# TSC_PROIECT_SCHEMATIC.net
KiCad netlist of a schematic drawn in EAGLE
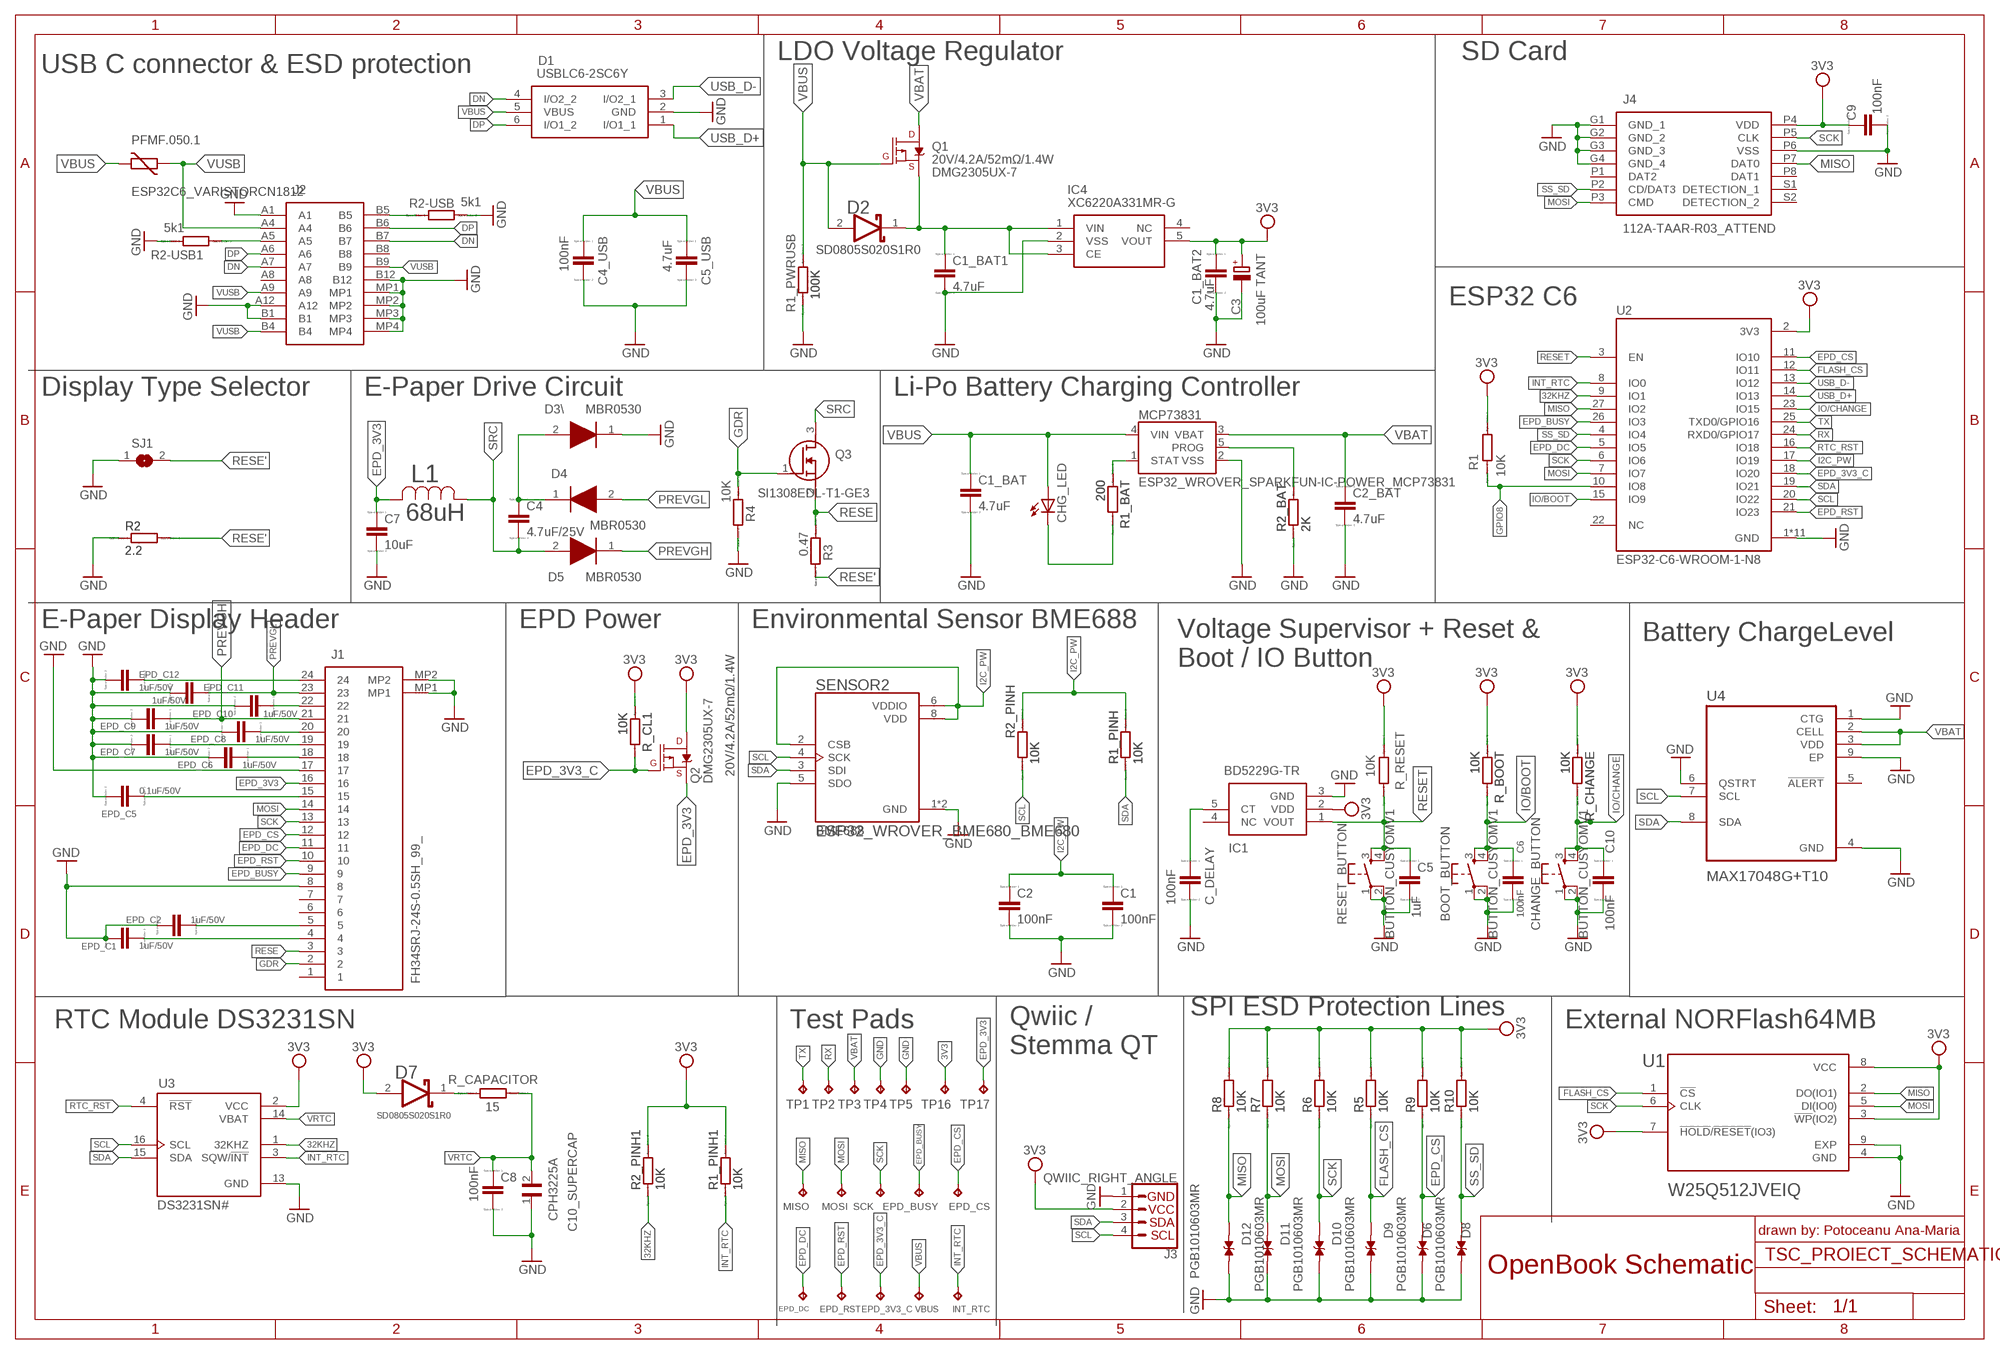
[diagram p0: schematic, sheet 1]

(export (version "E")
  (design (tool "Eeschema 10.0.6"))
  (components
    (comp (ref "BOOT_BUTTON")
      (value "BUTTON_CUSYOMV1")
      (footprint "eagle-import:MYBUTTON")
      (libsource (lib "eagle-import") (part "BUTTON_CUSYOMV1"))
    )
    (comp (ref "C1")
      (value "100nF")
      (footprint "eagle-import:ESP32_WROVER_EAGLE-LTSPICE_C0402")
      (libsource (lib "eagle-import") (part "ESP32_WROVER_EAGLE-LTSPICE_CC0402"))
    )
    (comp (ref "C1_BAT")
      (value "4.7uF")
      (footprint "eagle-import:ESP32_WROVER_EAGLE-LTSPICE_C0402")
      (libsource (lib "eagle-import") (part "EAGLE-LTSPICE_CC0402"))
    )
    (comp (ref "C1_BAT1")
      (value "4.7uF")
      (footprint "eagle-import:ESP32_WROVER_EAGLE-LTSPICE_C0402")
      (libsource (lib "eagle-import") (part "EAGLE-LTSPICE_CC0402"))
    )
    (comp (ref "C1_BAT2")
      (value "4.7uF")
      (footprint "eagle-import:ESP32_WROVER_EAGLE-LTSPICE_C0402")
      (libsource (lib "eagle-import") (part "ESP32_WROVER_EAGLE-LTSPICE_CC0402"))
    )
    (comp (ref "C2")
      (value "100nF")
      (footprint "eagle-import:ESP32_WROVER_EAGLE-LTSPICE_C0402")
      (libsource (lib "eagle-import") (part "ESP32_WROVER_EAGLE-LTSPICE_CC0402"))
    )
    (comp (ref "C2_BAT")
      (value "4.7uF")
      (footprint "eagle-import:ESP32_WROVER_EAGLE-LTSPICE_C0402")
      (libsource (lib "eagle-import") (part "EAGLE-LTSPICE_CC0402"))
    )
    (comp (ref "C3")
      (value "100uF TANT")
      (footprint "eagle-import:RCL_CT3528")
      (libsource (lib "eagle-import") (part "RCL_CPOL-EUCT3528"))
    )
    (comp (ref "C4")
      (value "4.7uF/25V")
      (footprint "eagle-import:ESP32_WROVER_EAGLE-LTSPICE_C0402")
      (libsource (lib "eagle-import") (part "ESP32_WROVER_EAGLE-LTSPICE_CC0402"))
    )
    (comp (ref "C4_USB")
      (value "100nF")
      (footprint "eagle-import:ESP32_WROVER_EAGLE-LTSPICE_C0402")
      (libsource (lib "eagle-import") (part "ESP32_WROVER_EAGLE-LTSPICE_CC0402"))
    )
    (comp (ref "C5")
      (value "1uF")
      (footprint "eagle-import:ESP32_WROVER_EAGLE-LTSPICE_C0402")
      (libsource (lib "eagle-import") (part "EAGLE-LTSPICE_CC0402"))
    )
    (comp (ref "C5_USB")
      (value "4.7uF")
      (footprint "eagle-import:ESP32_WROVER_EAGLE-LTSPICE_C0402")
      (libsource (lib "eagle-import") (part "ESP32_WROVER_EAGLE-LTSPICE_CC0402"))
    )
    (comp (ref "C6")
      (value "100nF")
      (footprint "eagle-import:ESP32_WROVER_EAGLE-LTSPICE_C0402")
      (libsource (lib "eagle-import") (part "EAGLE-LTSPICE_CC0402"))
    )
    (comp (ref "C7")
      (value "10uF")
      (footprint "eagle-import:ESP32_WROVER_EAGLE-LTSPICE_C0402")
      (libsource (lib "eagle-import") (part "ESP32_WROVER_EAGLE-LTSPICE_CC0402"))
    )
    (comp (ref "C8")
      (value "100nF")
      (footprint "eagle-import:ESP32_WROVER_EAGLE-LTSPICE_C0402")
      (libsource (lib "eagle-import") (part "ESP32_WROVER_EAGLE-LTSPICE_CC0402"))
    )
    (comp (ref "C9")
      (value "100nF")
      (footprint "eagle-import:ESP32_WROVER_EAGLE-LTSPICE_C0402")
      (libsource (lib "eagle-import") (part "EAGLE-LTSPICE_CC0402"))
    )
    (comp (ref "C10")
      (value "100nF")
      (footprint "eagle-import:ESP32_WROVER_EAGLE-LTSPICE_C0402")
      (libsource (lib "eagle-import") (part "EAGLE-LTSPICE_CC0402"))
    )
    (comp (ref "C10_SUPERCAP")
      (value "CPH3225A")
      (footprint "eagle-import:CAPCP3225X100N")
      (fields (field (name "MF") "Seiko Instruments"))
      (libsource (lib "eagle-import") (part "CPH3225A"))
    )
    (comp (ref "CHANGE_BUTTON")
      (value "BUTTON_CUSYOMV1")
      (footprint "eagle-import:MYBUTTON")
      (libsource (lib "eagle-import") (part "BUTTON_CUSYOMV1"))
    )
    (comp (ref "CHG_LED")
      (value "ADAFRUIT_LEDCHIP-LED0603")
      (footprint "eagle-import:ADAFRUIT_CHIP-LED0603")
      (libsource (lib "eagle-import") (part "ADAFRUIT_LEDCHIP-LED0603"))
    )
    (comp (ref "C_DELAY")
      (value "100nF")
      (footprint "eagle-import:ESP32_WROVER_EAGLE-LTSPICE_C0402")
      (libsource (lib "eagle-import") (part "EAGLE-LTSPICE_CC0402"))
    )
    (comp (ref "D1")
      (value "USBLC6-2SC6Y")
      (footprint "eagle-import:SOT95P280X145-6N")
      (fields (field (name "MF") "STMicroelectronics"))
      (libsource (lib "eagle-import") (part "USBLC6-2SC6Y"))
    )
    (comp (ref "D2")
      (value "ESP32_WROVER_AVX---SD0805S020S1R0_AVX_SD0805S020S1R0_0_0AVX_SD0805S020S1R0_0_0")
      (footprint "eagle-import:ESP32_WROVER_AVX---SD0805S020S1R0_AVX_SD0805S020S1R0_0")
      (fields
        (field (name "DIGIKEY_PART_NUMBER") "478-7800-1-ND")
        (field (name "MF") "AVX")
        (field (name "MOUSER_PART_NUMBER") "581-SD0805S020S1R0")
      )
      (libsource (lib "eagle-import") (part "ESP32_WROVER_AVX---SD0805S020S1R0_AVX_SD0805S020S1R0_0_0AVX_SD0805S020S1R0_0_0"))
    )
    (comp (ref "D3\\")
      (value "MBR0530")
      (footprint "eagle-import:SOD3716X135N")
      (fields (field (name "MF") "ON Semiconductor"))
      (libsource (lib "eagle-import") (part "MBR0530"))
    )
    (comp (ref "D4")
      (value "MBR0530")
      (footprint "eagle-import:SOD3716X135N")
      (fields (field (name "MF") "ON Semiconductor"))
      (libsource (lib "eagle-import") (part "MBR0530"))
    )
    (comp (ref "D5")
      (value "MBR0530")
      (footprint "eagle-import:SOD3716X135N")
      (fields (field (name "MF") "ON Semiconductor"))
      (libsource (lib "eagle-import") (part "MBR0530"))
    )
    (comp (ref "D6")
      (value "PGB1010603MR")
      (footprint "eagle-import:DIOC1608X36N")
      (fields (field (name "MF") "Littelfuse Inc."))
      (libsource (lib "eagle-import") (part "PGB1010603MR"))
    )
    (comp (ref "D7")
      (value "ESP32_WROVER_AVX---SD0805S020S1R0_AVX_SD0805S020S1R0_0_0AVX_SD0805S020S1R0_0_0")
      (footprint "eagle-import:ESP32_WROVER_AVX---SD0805S020S1R0_AVX_SD0805S020S1R0_0")
      (fields
        (field (name "DIGIKEY_PART_NUMBER") "478-7800-1-ND")
        (field (name "MF") "AVX")
        (field (name "MOUSER_PART_NUMBER") "581-SD0805S020S1R0")
      )
      (libsource (lib "eagle-import") (part "ESP32_WROVER_AVX---SD0805S020S1R0_AVX_SD0805S020S1R0_0_0AVX_SD0805S020S1R0_0_0"))
    )
    (comp (ref "D8")
      (value "PGB1010603MR")
      (footprint "eagle-import:DIOC1608X36N")
      (fields (field (name "MF") "Littelfuse Inc."))
      (libsource (lib "eagle-import") (part "PGB1010603MR"))
    )
    (comp (ref "D9")
      (value "PGB1010603MR")
      (footprint "eagle-import:DIOC1608X36N")
      (fields (field (name "MF") "Littelfuse Inc."))
      (libsource (lib "eagle-import") (part "PGB1010603MR"))
    )
    (comp (ref "D10")
      (value "PGB1010603MR")
      (footprint "eagle-import:DIOC1608X36N")
      (fields (field (name "MF") "Littelfuse Inc."))
      (libsource (lib "eagle-import") (part "PGB1010603MR"))
    )
    (comp (ref "D11")
      (value "PGB1010603MR")
      (footprint "eagle-import:DIOC1608X36N")
      (fields (field (name "MF") "Littelfuse Inc."))
      (libsource (lib "eagle-import") (part "PGB1010603MR"))
    )
    (comp (ref "D12")
      (value "PGB1010603MR")
      (footprint "eagle-import:DIOC1608X36N")
      (fields (field (name "MF") "Littelfuse Inc."))
      (libsource (lib "eagle-import") (part "PGB1010603MR"))
    )
    (comp (ref "EPD_3V3_C")
      (value "TPTP20R")
      (footprint "eagle-import:TP20R")
      (libsource (lib "eagle-import") (part "TPTP20R"))
    )
    (comp (ref "EPD_BUSY")
      (value "TPTP20R")
      (footprint "eagle-import:TP20R")
      (libsource (lib "eagle-import") (part "TPTP20R"))
    )
    (comp (ref "EPD_C1")
      (value "1uF/50V")
      (footprint "eagle-import:ESP32_WROVER_EAGLE-LTSPICE_C0402")
      (libsource (lib "eagle-import") (part "EAGLE-LTSPICE_CC0402"))
    )
    (comp (ref "EPD_C2")
      (value "1uF/50V")
      (footprint "eagle-import:ESP32_WROVER_EAGLE-LTSPICE_C0402")
      (libsource (lib "eagle-import") (part "EAGLE-LTSPICE_CC0402"))
    )
    (comp (ref "EPD_C5")
      (value "0.1uF/50V")
      (footprint "eagle-import:ESP32_WROVER_EAGLE-LTSPICE_C0402")
      (libsource (lib "eagle-import") (part "ESP32_WROVER_EAGLE-LTSPICE_CC0402"))
    )
    (comp (ref "EPD_C6")
      (value "1uF/50V")
      (footprint "eagle-import:ESP32_WROVER_EAGLE-LTSPICE_C0402")
      (libsource (lib "eagle-import") (part "ESP32_WROVER_EAGLE-LTSPICE_CC0402"))
    )
    (comp (ref "EPD_C7")
      (value "1uF/50V")
      (footprint "eagle-import:ESP32_WROVER_EAGLE-LTSPICE_C0402")
      (libsource (lib "eagle-import") (part "ESP32_WROVER_EAGLE-LTSPICE_CC0402"))
    )
    (comp (ref "EPD_C8")
      (value "1uF/50V")
      (footprint "eagle-import:ESP32_WROVER_EAGLE-LTSPICE_C0402")
      (libsource (lib "eagle-import") (part "ESP32_WROVER_EAGLE-LTSPICE_CC0402"))
    )
    (comp (ref "EPD_C9")
      (value "1uF/50V")
      (footprint "eagle-import:ESP32_WROVER_EAGLE-LTSPICE_C0402")
      (libsource (lib "eagle-import") (part "ESP32_WROVER_EAGLE-LTSPICE_CC0402"))
    )
    (comp (ref "EPD_C10")
      (value "1uF/50V")
      (footprint "eagle-import:ESP32_WROVER_EAGLE-LTSPICE_C0402")
      (libsource (lib "eagle-import") (part "ESP32_WROVER_EAGLE-LTSPICE_CC0402"))
    )
    (comp (ref "EPD_C11")
      (value "1uF/50V")
      (footprint "eagle-import:ESP32_WROVER_EAGLE-LTSPICE_C0402")
      (libsource (lib "eagle-import") (part "ESP32_WROVER_EAGLE-LTSPICE_CC0402"))
    )
    (comp (ref "EPD_C12")
      (value "1uF/50V")
      (footprint "eagle-import:ESP32_WROVER_EAGLE-LTSPICE_C0402")
      (libsource (lib "eagle-import") (part "ESP32_WROVER_EAGLE-LTSPICE_CC0402"))
    )
    (comp (ref "EPD_CS")
      (value "TPTP20R")
      (footprint "eagle-import:TP20R")
      (libsource (lib "eagle-import") (part "TPTP20R"))
    )
    (comp (ref "EPD_DC")
      (value "TPTP20R")
      (footprint "eagle-import:TP20R")
      (libsource (lib "eagle-import") (part "TPTP20R"))
    )
    (comp (ref "EPD_RST")
      (value "TPTP20R")
      (footprint "eagle-import:TP20R")
      (libsource (lib "eagle-import") (part "TPTP20R"))
    )
    (comp (ref "IC1")
      (value "BD5229G-TR")
      (footprint "eagle-import:SOT95P280X125-5N")
      (fields (field (name "MOUSER_PART_NUMBER") "755-BD5229G-TR"))
      (libsource (lib "eagle-import") (part "BD5229G-TR"))
    )
    (comp (ref "IC4")
      (value "XC6220A331MR-G")
      (footprint "eagle-import:SOT95P280X120-5N")
      (fields (field (name "MOUSER_PART_NUMBER") "865-XC6220A331MR-G"))
      (libsource (lib "eagle-import") (part "XC6220A331MR-G"))
    )
    (comp (ref "INT_RTC")
      (value "TPTP20R")
      (footprint "eagle-import:TP20R")
      (libsource (lib "eagle-import") (part "TPTP20R"))
    )
    (comp (ref "J1")
      (value "FH34SRJ-24S-0.5SH_99_")
      (footprint "eagle-import:FH34SRJ24S05SH99")
      (fields
        (field (name "MANUFACTURER_PART_NUMBER") "FH34SRJ-24S-0.5SH(99)")
        (field (name "MOUSER_PART_NUMBER") "798-FH34SRJ24S05SH99")
      )
      (libsource (lib "eagle-import") (part "FH34SRJ-24S-0.5SH_99_"))
    )
    (comp (ref "J2")
      (value "SAMACSYS_PARTS_USB4110-GF-A")
      (footprint "eagle-import:SAMACSYS_PARTS_USB4110GFA")
      (fields
        (field (name "MANUFACTURER_PART_NUMBER") "USB4110-GF-A")
        (field (name "MOUSER_PART_NUMBER") "640-USB4110-GF-A")
      )
      (libsource (lib "eagle-import") (part "SAMACSYS_PARTS_USB4110-GF-A"))
    )
    (comp (ref "J3")
      (value "QWIIC_RIGHT_ANGLE")
      (footprint "eagle-import:JST04_1MM_RA")
      (libsource (lib "eagle-import") (part "QWIIC_CONNECTORJS-1MM"))
    )
    (comp (ref "J4")
      (value "112A-TAAR-R03_ATTEND")
      (footprint "eagle-import:112ATAARR03ATTEND")
      (fields (field (name "MANUFACTURER_PART_NUMBER") "112A-TAAR-R03 ATTEND"))
      (libsource (lib "eagle-import") (part "112A-TAAR-R03_ATTEND"))
    )
    (comp (ref "L1")
      (value "68uH")
      (footprint "eagle-import:IND_4828-WE-TPC_WRE")
      (fields
        (field (name "MANUFACTURER_PART_NUMBER") "744043680")
        (field (name "COPYRIGHT") "Copyright (C) 2024 Ultra Librarian. All rights reserved.")
      )
      (libsource (lib "eagle-import") (part "744043680IND_4828-WE-TPC_WRE"))
    )
    (comp (ref "MCP73831")
      (value "ESP32_WROVER_SPARKFUN-IC-POWER_MCP73831")
      (footprint "eagle-import:ESP32_WROVER_SPARKFUN-IC-POWER_SOT23-5")
      (libsource (lib "eagle-import") (part "ESP32_WROVER_SPARKFUN-IC-POWER_MCP73831"))
    )
    (comp (ref "MISO")
      (value "TPTP20R")
      (footprint "eagle-import:TP20R")
      (libsource (lib "eagle-import") (part "TPTP20R"))
    )
    (comp (ref "MOSI")
      (value "TPTP20R")
      (footprint "eagle-import:TP20R")
      (libsource (lib "eagle-import") (part "TPTP20R"))
    )
    (comp (ref "PFMF.050.1")
      (value "ESP32C6_VARISTORCN1812")
      (footprint "eagle-import:ESP32C6_VARISTOR_CT_CN1812")
      (libsource (lib "eagle-import") (part "ESP32C6_VARISTORCN1812"))
    )
    (comp (ref "Q1")
      (value "20V/4.2A/52mΩ/1.4W")
      (footprint "eagle-import:ESP32_WROVER_SPARKFUN-DISCRETESEMI_SOT23-3")
      (libsource (lib "eagle-import") (part "ESP32_WROVER_SPARKFUN-DISCRETESEMI_MOSFET_PCH-DMG2305UX-7"))
    )
    (comp (ref "Q2")
      (value "20V/4.2A/52mΩ/1.4W")
      (footprint "eagle-import:ESP32_WROVER_SPARKFUN-DISCRETESEMI_SOT23-3")
      (libsource (lib "eagle-import") (part "ESP32_WROVER_SPARKFUN-DISCRETESEMI_MOSFET_PCH-DMG2305UX-7"))
    )
    (comp (ref "Q3")
      (value "SI1308EDL-T1-GE3")
      (footprint "eagle-import:SOT65P210X110-3N")
      (fields (field (name "MF") "Vishay Siliconix"))
      (libsource (lib "eagle-import") (part "SI1308EDL-T1-GE3"))
    )
    (comp (ref "R1")
      (value "10K")
      (footprint "eagle-import:ESP32_WROVER_EAGLE-LTSPICE_R0402")
      (libsource (lib "eagle-import") (part "ESP32_WROVER_EAGLE-LTSPICE_RR0402"))
    )
    (comp (ref "R1_BAT")
      (value "200")
      (footprint "eagle-import:ESP32_WROVER_EAGLE-LTSPICE_R0402")
      (libsource (lib "eagle-import") (part "ESP32_WROVER_EAGLE-LTSPICE_RR0402"))
    )
    (comp (ref "R1_PINH")
      (value "10K")
      (footprint "eagle-import:ESP32_WROVER_EAGLE-LTSPICE_R0402")
      (libsource (lib "eagle-import") (part "ESP32_WROVER_EAGLE-LTSPICE_RR0402"))
    )
    (comp (ref "R1_PINH1")
      (value "10K")
      (footprint "eagle-import:ESP32_WROVER_EAGLE-LTSPICE_R0402")
      (libsource (lib "eagle-import") (part "ESP32_WROVER_EAGLE-LTSPICE_RR0402"))
    )
    (comp (ref "R1_PWRUSB")
      (value "100K")
      (footprint "eagle-import:ESP32_WROVER_EAGLE-LTSPICE_R0402")
      (libsource (lib "eagle-import") (part "ESP32_WROVER_EAGLE-LTSPICE_RR0402"))
    )
    (comp (ref "R2")
      (value "2.2")
      (footprint "eagle-import:ESP32_WROVER_EAGLE-LTSPICE_R0402")
      (libsource (lib "eagle-import") (part "ESP32_WROVER_EAGLE-LTSPICE_RR0402"))
    )
    (comp (ref "R2-USB")
      (value "5k1")
      (footprint "eagle-import:ESP32_WROVER_EAGLE-LTSPICE_R0402")
      (libsource (lib "eagle-import") (part "ESP32_WROVER_EAGLE-LTSPICE_RR0402"))
    )
    (comp (ref "R2-USB1")
      (value "5k1")
      (footprint "eagle-import:ESP32_WROVER_EAGLE-LTSPICE_R0402")
      (libsource (lib "eagle-import") (part "ESP32_WROVER_EAGLE-LTSPICE_RR0402"))
    )
    (comp (ref "R2_BAT")
      (value "2K")
      (footprint "eagle-import:ESP32_WROVER_EAGLE-LTSPICE_R0402")
      (libsource (lib "eagle-import") (part "ESP32_WROVER_EAGLE-LTSPICE_RR0402"))
    )
    (comp (ref "R2_PINH")
      (value "10K")
      (footprint "eagle-import:ESP32_WROVER_EAGLE-LTSPICE_R0402")
      (libsource (lib "eagle-import") (part "ESP32_WROVER_EAGLE-LTSPICE_RR0402"))
    )
    (comp (ref "R2_PINH1")
      (value "10K")
      (footprint "eagle-import:ESP32_WROVER_EAGLE-LTSPICE_R0402")
      (libsource (lib "eagle-import") (part "ESP32_WROVER_EAGLE-LTSPICE_RR0402"))
    )
    (comp (ref "R3")
      (value "0.47")
      (footprint "eagle-import:ESP32_WROVER_EAGLE-LTSPICE_R0402")
      (libsource (lib "eagle-import") (part "ESP32_WROVER_EAGLE-LTSPICE_RR0402"))
    )
    (comp (ref "R4")
      (value "10K")
      (footprint "eagle-import:ESP32_WROVER_EAGLE-LTSPICE_R0402")
      (libsource (lib "eagle-import") (part "ESP32_WROVER_EAGLE-LTSPICE_RR0402"))
    )
    (comp (ref "R5")
      (value "10K")
      (footprint "eagle-import:ESP32_WROVER_EAGLE-LTSPICE_R0402")
      (libsource (lib "eagle-import") (part "ESP32_WROVER_EAGLE-LTSPICE_RR0402"))
    )
    (comp (ref "R6")
      (value "10K")
      (footprint "eagle-import:ESP32_WROVER_EAGLE-LTSPICE_R0402")
      (libsource (lib "eagle-import") (part "ESP32_WROVER_EAGLE-LTSPICE_RR0402"))
    )
    (comp (ref "R7")
      (value "10K")
      (footprint "eagle-import:ESP32_WROVER_EAGLE-LTSPICE_R0402")
      (libsource (lib "eagle-import") (part "ESP32_WROVER_EAGLE-LTSPICE_RR0402"))
    )
    (comp (ref "R8")
      (value "10K")
      (footprint "eagle-import:ESP32_WROVER_EAGLE-LTSPICE_R0402")
      (libsource (lib "eagle-import") (part "ESP32_WROVER_EAGLE-LTSPICE_RR0402"))
    )
    (comp (ref "R9")
      (value "10K")
      (footprint "eagle-import:ESP32_WROVER_EAGLE-LTSPICE_R0402")
      (libsource (lib "eagle-import") (part "ESP32_WROVER_EAGLE-LTSPICE_RR0402"))
    )
    (comp (ref "R10")
      (value "10K")
      (footprint "eagle-import:ESP32_WROVER_EAGLE-LTSPICE_R0402")
      (libsource (lib "eagle-import") (part "ESP32_WROVER_EAGLE-LTSPICE_RR0402"))
    )
    (comp (ref "RESET_BUTTON")
      (value "BUTTON_CUSYOMV1")
      (footprint "eagle-import:MYBUTTON")
      (libsource (lib "eagle-import") (part "BUTTON_CUSYOMV1"))
    )
    (comp (ref "R_BOOT")
      (value "10K")
      (footprint "eagle-import:ESP32_WROVER_EAGLE-LTSPICE_R0402")
      (libsource (lib "eagle-import") (part "ESP32_WROVER_EAGLE-LTSPICE_RR0402"))
    )
    (comp (ref "R_CAPACITOR")
      (value "15")
      (footprint "eagle-import:ESP32_WROVER_EAGLE-LTSPICE_R0402")
      (libsource (lib "eagle-import") (part "ESP32_WROVER_EAGLE-LTSPICE_RR0402"))
    )
    (comp (ref "R_CHANGE")
      (value "10K")
      (footprint "eagle-import:ESP32_WROVER_EAGLE-LTSPICE_R0402")
      (libsource (lib "eagle-import") (part "ESP32_WROVER_EAGLE-LTSPICE_RR0402"))
    )
    (comp (ref "R_CL1")
      (value "10K")
      (footprint "eagle-import:ESP32_WROVER_EAGLE-LTSPICE_R0402")
      (libsource (lib "eagle-import") (part "ESP32_WROVER_EAGLE-LTSPICE_RR0402"))
    )
    (comp (ref "R_RESET")
      (value "10K")
      (footprint "eagle-import:ESP32_WROVER_EAGLE-LTSPICE_R0402")
      (libsource (lib "eagle-import") (part "ESP32_WROVER_EAGLE-LTSPICE_RR0402"))
    )
    (comp (ref "SCK")
      (value "TPTP20R")
      (footprint "eagle-import:TP20R")
      (libsource (lib "eagle-import") (part "TPTP20R"))
    )
    (comp (ref "SENSOR2")
      (value "ESP32_WROVER_BME680_BME680")
      (footprint "eagle-import:ESP32_WROVER_BME680_PSON80P300X300X100-8N")
      (fields (field (name "MF") "Bosch Sensortec") (field (name "MP") "BME680"))
      (libsource (lib "eagle-import") (part "ESP32_WROVER_BME680_BME680"))
    )
    (comp (ref "SJ1") (value "SJ") (footprint "eagle-import:SJ") (libsource (lib "eagle-import") (part "SJ")))
    (comp (ref "TP1")
      (value "TPTP20R")
      (footprint "eagle-import:TP20R")
      (libsource (lib "eagle-import") (part "TPTP20R"))
    )
    (comp (ref "TP2")
      (value "TPTP20R")
      (footprint "eagle-import:TP20R")
      (libsource (lib "eagle-import") (part "TPTP20R"))
    )
    (comp (ref "TP3")
      (value "TPTP20R")
      (footprint "eagle-import:TP20R")
      (libsource (lib "eagle-import") (part "TPTP20R"))
    )
    (comp (ref "TP4")
      (value "TPTP20R")
      (footprint "eagle-import:TP20R")
      (libsource (lib "eagle-import") (part "TPTP20R"))
    )
    (comp (ref "TP5")
      (value "TPTP20R")
      (footprint "eagle-import:TP20R")
      (libsource (lib "eagle-import") (part "TPTP20R"))
    )
    (comp (ref "TP16")
      (value "TPTP20R")
      (footprint "eagle-import:TP20R")
      (libsource (lib "eagle-import") (part "TPTP20R"))
    )
    (comp (ref "TP17")
      (value "TPTP20R")
      (footprint "eagle-import:TP20R")
      (libsource (lib "eagle-import") (part "TPTP20R"))
    )
    (comp (ref "U1")
      (value "W25Q512JVEIQ")
      (footprint "eagle-import:SON127P600X800X80-9N")
      (fields (field (name "MF") "Winbond Electronics"))
      (libsource (lib "eagle-import") (part "W25Q512JVEIQ"))
    )
    (comp (ref "U2")
      (value "ESP32-C6-WROOM-1-N8")
      (footprint "eagle-import:XCVR_ESP32-C6-WROOM-1-N8")
      (fields (field (name "MF") "Espressif Systems"))
      (libsource (lib "eagle-import") (part "ESP32-C6-WROOM-1-N8"))
    )
    (comp (ref "U3")
      (value "DS3231SN#")
      (footprint "eagle-import:SOIC127P1032X265-16N")
      (fields (field (name "MF") "Analog Devices"))
      (libsource (lib "eagle-import") (part "DS3231SN#"))
    )
    (comp (ref "U4")
      (value "MAX17048G+T10")
      (footprint "eagle-import:SON50P200X200X80-9N")
      (fields (field (name "MF") "Analog Devices"))
      (libsource (lib "eagle-import") (part "MAX17048G+T10"))
    )
    (comp (ref "VBUS")
      (value "TPTP20R")
      (footprint "eagle-import:TP20R")
      (libsource (lib "eagle-import") (part "TPTP20R"))
    )
  )
  (nets
    (net (code "1") (name "3V3") (class "Default")
      (node (ref "C1_BAT2") (pin "1") (pinfunction "1_1") (pintype "passive"))
      (node (ref "C3") (pin "+") (pinfunction "+_+") (pintype "passive"))
      (node (ref "C9") (pin "1") (pinfunction "1_1") (pintype "passive"))
      (node (ref "D7") (pin "2") (pinfunction "ANODE_2") (pintype "bidirectional"))
      (node (ref "IC1") (pin "2") (pinfunction "VDD_2") (pintype "bidirectional"))
      (node (ref "IC4") (pin "5") (pinfunction "VOUT_5") (pintype "bidirectional"))
      (node (ref "J3") (pin "2") (pinfunction "2_2") (pintype "power_in"))
      (node (ref "J4") (pin "P4") (pinfunction "VDD_P4") (pintype "bidirectional"))
      (node (ref "Q2") (pin "3") (pinfunction "D_3") (pintype "bidirectional"))
      (node (ref "R1") (pin "1") (pinfunction "1_1") (pintype "passive"))
      (node (ref "R10") (pin "2") (pinfunction "2_2") (pintype "passive"))
      (node (ref "R1_PINH1") (pin "2") (pinfunction "2_2") (pintype "passive"))
      (node (ref "R2_PINH1") (pin "2") (pinfunction "2_2") (pintype "passive"))
      (node (ref "R5") (pin "2") (pinfunction "2_2") (pintype "passive"))
      (node (ref "R6") (pin "2") (pinfunction "2_2") (pintype "passive"))
      (node (ref "R7") (pin "2") (pinfunction "2_2") (pintype "passive"))
      (node (ref "R8") (pin "2") (pinfunction "2_2") (pintype "passive"))
      (node (ref "R9") (pin "2") (pinfunction "2_2") (pintype "passive"))
      (node (ref "R_BOOT") (pin "1") (pinfunction "1_1") (pintype "passive"))
      (node (ref "R_CHANGE") (pin "1") (pinfunction "1_1") (pintype "passive"))
      (node (ref "R_CL1") (pin "1") (pinfunction "1_1") (pintype "passive"))
      (node (ref "R_RESET") (pin "1") (pinfunction "1_1") (pintype "passive"))
      (node (ref "TP16") (pin "TP") (pinfunction "TP_TP") (pintype "input"))
      (node (ref "U1") (pin "3") (pinfunction "~{WP}(IO2)_3") (pintype "bidirectional"))
      (node (ref "U1") (pin "7") (pinfunction "~{HOLD}/~{RESET}(IO3)_7") (pintype "bidirectional"))
      (node (ref "U1") (pin "8") (pinfunction "VCC_8") (pintype "power_in"))
      (node (ref "U2") (pin "2") (pinfunction "3V3_2") (pintype "power_in"))
      (node (ref "U3") (pin "2") (pinfunction "VCC_2") (pintype "power_in"))
    )
    (net (code "2") (name "32KHZ") (class "Default")
      (node (ref "R2_PINH1") (pin "1") (pinfunction "1_1") (pintype "passive"))
      (node (ref "U2") (pin "9") (pinfunction "IO1_9") (pintype "bidirectional"))
      (node (ref "U3") (pin "1") (pinfunction "32KHZ_1") (pintype "output"))
    )
    (net (code "3") (name "DN") (class "Default")
      (node (ref "D1") (pin "4") (pinfunction "I/O2_2_4") (pintype "bidirectional"))
      (node (ref "J2") (pin "A7") (pinfunction "A7_A7") (pintype "bidirectional"))
      (node (ref "J2") (pin "B7") (pinfunction "B7_B7") (pintype "bidirectional"))
    )
    (net (code "4") (name "DP") (class "Default")
      (node (ref "D1") (pin "6") (pinfunction "I/O1_2_6") (pintype "bidirectional"))
      (node (ref "J2") (pin "A6") (pinfunction "A6_A6") (pintype "bidirectional"))
      (node (ref "J2") (pin "B6") (pinfunction "B6_B6") (pintype "bidirectional"))
    )
    (net (code "5") (name "EPD_3V3") (class "Default")
      (node (ref "C7") (pin "1") (pinfunction "1_1") (pintype "passive"))
      (node (ref "J1") (pin "16") (pinfunction "16_16") (pintype "bidirectional"))
      (node (ref "L1") (pin "2") (pinfunction "2_2") (pintype "passive"))
      (node (ref "Q2") (pin "2") (pinfunction "S_2") (pintype "bidirectional"))
      (node (ref "TP17") (pin "TP") (pinfunction "TP_TP") (pintype "input"))
    )
    (net (code "6") (name "EPD_3V3_C") (class "Default")
      (node (ref "EPD_3V3_C") (pin "TP") (pinfunction "TP_TP") (pintype "input"))
      (node (ref "Q2") (pin "1") (pinfunction "G_1") (pintype "bidirectional"))
      (node (ref "R_CL1") (pin "2") (pinfunction "2_2") (pintype "passive"))
      (node (ref "U2") (pin "18") (pinfunction "IO20_18") (pintype "bidirectional"))
    )
    (net (code "7") (name "EPD_BUSY") (class "Default")
      (node (ref "EPD_BUSY") (pin "TP") (pinfunction "TP_TP") (pintype "input"))
      (node (ref "J1") (pin "9") (pinfunction "9_9") (pintype "bidirectional"))
      (node (ref "U2") (pin "26") (pinfunction "IO3_26") (pintype "bidirectional"))
    )
    (net (code "8") (name "EPD_CS") (class "Default")
      (node (ref "D6") (pin "1") (pinfunction "1_1") (pintype "passive"))
      (node (ref "EPD_CS") (pin "TP") (pinfunction "TP_TP") (pintype "input"))
      (node (ref "J1") (pin "12") (pinfunction "12_12") (pintype "bidirectional"))
      (node (ref "R9") (pin "1") (pinfunction "1_1") (pintype "passive"))
      (node (ref "U2") (pin "11") (pinfunction "IO10_11") (pintype "bidirectional"))
    )
    (net (code "9") (name "EPD_DC") (class "Default")
      (node (ref "EPD_DC") (pin "TP") (pinfunction "TP_TP") (pintype "input"))
      (node (ref "J1") (pin "11") (pinfunction "11_11") (pintype "bidirectional"))
      (node (ref "U2") (pin "5") (pinfunction "IO5_5") (pintype "bidirectional"))
    )
    (net (code "10") (name "EPD_RST") (class "Default")
      (node (ref "EPD_RST") (pin "TP") (pinfunction "TP_TP") (pintype "input"))
      (node (ref "J1") (pin "10") (pinfunction "10_10") (pintype "bidirectional"))
      (node (ref "U2") (pin "21") (pinfunction "IO23_21") (pintype "bidirectional"))
    )
    (net (code "11") (name "FLASH_CS") (class "Default")
      (node (ref "D9") (pin "1") (pinfunction "1_1") (pintype "passive"))
      (node (ref "R5") (pin "1") (pinfunction "1_1") (pintype "passive"))
      (node (ref "U1") (pin "1") (pinfunction "~{CS}_1") (pintype "input"))
      (node (ref "U2") (pin "12") (pinfunction "IO11_12") (pintype "bidirectional"))
    )
    (net (code "12") (name "GDR") (class "Default")
      (node (ref "J1") (pin "2") (pinfunction "2_2") (pintype "bidirectional"))
      (node (ref "Q3") (pin "1") (pinfunction "G_1") (pintype "bidirectional"))
      (node (ref "R4") (pin "1") (pinfunction "1_1") (pintype "passive"))
    )
    (net (code "13") (name "GND") (class "Default")
      (node (ref "BOOT_BUTTON") (pin "1") (pinfunction "1_1") (pintype "passive"))
      (node (ref "BOOT_BUTTON") (pin "2") (pinfunction "2_2") (pintype "passive"))
      (node (ref "C1") (pin "2") (pinfunction "2_2") (pintype "passive"))
      (node (ref "C10") (pin "2") (pinfunction "2_2") (pintype "passive"))
      (node (ref "C10_SUPERCAP") (pin "1") (pinfunction "1_1") (pintype "passive"))
      (node (ref "C1_BAT") (pin "2") (pinfunction "2_2") (pintype "passive"))
      (node (ref "C1_BAT1") (pin "2") (pinfunction "2_2") (pintype "passive"))
      (node (ref "C1_BAT2") (pin "2") (pinfunction "2_2") (pintype "passive"))
      (node (ref "C2") (pin "2") (pinfunction "2_2") (pintype "passive"))
      (node (ref "C2_BAT") (pin "2") (pinfunction "2_2") (pintype "passive"))
      (node (ref "C3") (pin "-") (pinfunction "-_-") (pintype "passive"))
      (node (ref "C4_USB") (pin "2") (pinfunction "2_2") (pintype "passive"))
      (node (ref "C5") (pin "2") (pinfunction "2_2") (pintype "passive"))
      (node (ref "C5_USB") (pin "2") (pinfunction "2_2") (pintype "passive"))
      (node (ref "C6") (pin "2") (pinfunction "2_2") (pintype "passive"))
      (node (ref "C7") (pin "2") (pinfunction "2_2") (pintype "passive"))
      (node (ref "C8") (pin "2") (pinfunction "2_2") (pintype "passive"))
      (node (ref "C9") (pin "2") (pinfunction "2_2") (pintype "passive"))
      (node (ref "CHANGE_BUTTON") (pin "1") (pinfunction "1_1") (pintype "passive"))
      (node (ref "CHANGE_BUTTON") (pin "2") (pinfunction "2_2") (pintype "passive"))
      (node (ref "C_DELAY") (pin "2") (pinfunction "2_2") (pintype "passive"))
      (node (ref "D1") (pin "2") (pinfunction "GND_2") (pintype "bidirectional"))
      (node (ref "D10") (pin "2") (pinfunction "2_2") (pintype "passive"))
      (node (ref "D11") (pin "2") (pinfunction "2_2") (pintype "passive"))
      (node (ref "D12") (pin "2") (pinfunction "2_2") (pintype "passive"))
      (node (ref "D3\\") (pin "1") (pinfunction "K_1") (pintype "bidirectional"))
      (node (ref "D6") (pin "2") (pinfunction "2_2") (pintype "passive"))
      (node (ref "D8") (pin "2") (pinfunction "2_2") (pintype "passive"))
      (node (ref "D9") (pin "2") (pinfunction "2_2") (pintype "passive"))
      (node (ref "EPD_C1") (pin "2") (pinfunction "2_2") (pintype "passive"))
      (node (ref "EPD_C10") (pin "2") (pinfunction "2_2") (pintype "passive"))
      (node (ref "EPD_C11") (pin "2") (pinfunction "2_2") (pintype "passive"))
      (node (ref "EPD_C12") (pin "2") (pinfunction "2_2") (pintype "passive"))
      (node (ref "EPD_C2") (pin "2") (pinfunction "2_2") (pintype "passive"))
      (node (ref "EPD_C5") (pin "2") (pinfunction "2_2") (pintype "passive"))
      (node (ref "EPD_C6") (pin "2") (pinfunction "2_2") (pintype "passive"))
      (node (ref "EPD_C7") (pin "2") (pinfunction "2_2") (pintype "passive"))
      (node (ref "EPD_C8") (pin "2") (pinfunction "2_2") (pintype "passive"))
      (node (ref "EPD_C9") (pin "2") (pinfunction "2_2") (pintype "passive"))
      (node (ref "IC1") (pin "3") (pinfunction "GND_3") (pintype "bidirectional"))
      (node (ref "IC4") (pin "2") (pinfunction "VSS_2") (pintype "bidirectional"))
      (node (ref "J1") (pin "17") (pinfunction "17_17") (pintype "bidirectional"))
      (node (ref "J1") (pin "8") (pinfunction "8_8") (pintype "bidirectional"))
      (node (ref "J1") (pin "MP1") (pinfunction "MP1_MP1") (pintype "bidirectional"))
      (node (ref "J1") (pin "MP2") (pinfunction "MP2_MP2") (pintype "bidirectional"))
      (node (ref "J2") (pin "A1") (pinfunction "A1_A1") (pintype "bidirectional"))
      (node (ref "J2") (pin "A12") (pinfunction "A12_A12") (pintype "bidirectional"))
      (node (ref "J2") (pin "B1") (pinfunction "B1_B1") (pintype "bidirectional"))
      (node (ref "J2") (pin "B12") (pinfunction "B12_B12") (pintype "bidirectional"))
      (node (ref "J2") (pin "MP1") (pinfunction "MP1_MP1") (pintype "bidirectional"))
      (node (ref "J2") (pin "MP2") (pinfunction "MP2_MP2") (pintype "bidirectional"))
      (node (ref "J2") (pin "MP3") (pinfunction "MP3_MP3") (pintype "bidirectional"))
      (node (ref "J2") (pin "MP4") (pinfunction "MP4_MP4") (pintype "bidirectional"))
      (node (ref "J3") (pin "1") (pinfunction "1_1") (pintype "power_in"))
      (node (ref "J4") (pin "G1") (pinfunction "GND_1_G1") (pintype "bidirectional"))
      (node (ref "J4") (pin "G2") (pinfunction "GND_2_G2") (pintype "bidirectional"))
      (node (ref "J4") (pin "G3") (pinfunction "GND_3_G3") (pintype "bidirectional"))
      (node (ref "J4") (pin "G4") (pinfunction "GND_4_G4") (pintype "bidirectional"))
      (node (ref "J4") (pin "P6") (pinfunction "VSS_P6") (pintype "bidirectional"))
      (node (ref "MCP73831") (pin "2") (pinfunction "VSS_2") (pintype "power_in"))
      (node (ref "R1_PWRUSB") (pin "1") (pinfunction "1_1") (pintype "passive"))
      (node (ref "R2") (pin "1") (pinfunction "1_1") (pintype "passive"))
      (node (ref "R2-USB") (pin "2") (pinfunction "2_2") (pintype "passive"))
      (node (ref "R2-USB1") (pin "1") (pinfunction "1_1") (pintype "passive"))
      (node (ref "R2_BAT") (pin "1") (pinfunction "1_1") (pintype "passive"))
      (node (ref "R4") (pin "2") (pinfunction "2_2") (pintype "passive"))
      (node (ref "RESET_BUTTON") (pin "1") (pinfunction "1_1") (pintype "passive"))
      (node (ref "RESET_BUTTON") (pin "2") (pinfunction "2_2") (pintype "passive"))
      (node (ref "SENSOR2") (pin "1") (pinfunction "GND_1") (pintype "power_in"))
      (node (ref "SENSOR2") (pin "5") (pinfunction "SDO_5") (pintype "bidirectional"))
      (node (ref "SENSOR2") (pin "7") (pinfunction "GND_7") (pintype "power_in"))
      (node (ref "SJ1") (pin "1") (pinfunction "1_1") (pintype "passive"))
      (node (ref "TP4") (pin "TP") (pinfunction "TP_TP") (pintype "input"))
      (node (ref "TP5") (pin "TP") (pinfunction "TP_TP") (pintype "input"))
      (node (ref "U1") (pin "4") (pinfunction "GND_4") (pintype "power_in"))
      (node (ref "U1") (pin "9") (pinfunction "EXP_9") (pintype "passive"))
      (node (ref "U2") (pin "1") (pinfunction "GND_1") (pintype "power_in"))
      (node (ref "U2") (pin "28") (pinfunction "GND_28") (pintype "power_in"))
      (node (ref "U2") (pin "29_1") (pinfunction "GND_29_1") (pintype "power_in"))
      (node (ref "U2") (pin "29_2") (pinfunction "GND_29_2") (pintype "power_in"))
      (node (ref "U2") (pin "29_3") (pinfunction "GND_29_3") (pintype "power_in"))
      (node (ref "U2") (pin "29_4") (pinfunction "GND_29_4") (pintype "power_in"))
      (node (ref "U2") (pin "29_5") (pinfunction "GND_29_5") (pintype "power_in"))
      (node (ref "U2") (pin "29_6") (pinfunction "GND_29_6") (pintype "power_in"))
      (node (ref "U2") (pin "29_7") (pinfunction "GND_29_7") (pintype "power_in"))
      (node (ref "U2") (pin "29_8") (pinfunction "GND_29_8") (pintype "power_in"))
      (node (ref "U2") (pin "29_9") (pinfunction "GND_29_9") (pintype "power_in"))
      (node (ref "U3") (pin "13") (pinfunction "GND_13") (pintype "power_in"))
      (node (ref "U4") (pin "1") (pinfunction "CTG_1") (pintype "power_in"))
      (node (ref "U4") (pin "4") (pinfunction "GND_4") (pintype "power_in"))
      (node (ref "U4") (pin "6") (pinfunction "QSTRT_6") (pintype "input"))
      (node (ref "U4") (pin "9") (pinfunction "EP_9") (pintype "power_in"))
    )
    (net (code "14") (name "GPIO8") (class "Default")
      (node (ref "R1") (pin "2") (pinfunction "2_2") (pintype "passive"))
      (node (ref "U2") (pin "10") (pinfunction "IO8_10") (pintype "bidirectional"))
    )
    (net (code "15") (name "I2C_PW") (class "Default")
      (node (ref "C1") (pin "1") (pinfunction "1_1") (pintype "passive"))
      (node (ref "C2") (pin "1") (pinfunction "1_1") (pintype "passive"))
      (node (ref "R1_PINH") (pin "2") (pinfunction "2_2") (pintype "passive"))
      (node (ref "R2_PINH") (pin "2") (pinfunction "2_2") (pintype "passive"))
      (node (ref "SENSOR2") (pin "2") (pinfunction "CSB_2") (pintype "input"))
      (node (ref "SENSOR2") (pin "6") (pinfunction "VDDIO_6") (pintype "power_in"))
      (node (ref "SENSOR2") (pin "8") (pinfunction "VDD_8") (pintype "power_in"))
      (node (ref "U2") (pin "17") (pinfunction "IO19_17") (pintype "bidirectional"))
    )
    (net (code "16") (name "INT_RTC") (class "Default")
      (node (ref "INT_RTC") (pin "TP") (pinfunction "TP_TP") (pintype "input"))
      (node (ref "R1_PINH1") (pin "1") (pinfunction "1_1") (pintype "passive"))
      (node (ref "U2") (pin "8") (pinfunction "IO0_8") (pintype "bidirectional"))
      (node (ref "U3") (pin "3") (pinfunction "SQW/~{INT}_3") (pintype "output"))
    )
    (net (code "17") (name "IO{slash}BOOT") (class "Default")
      (node (ref "BOOT_BUTTON") (pin "3") (pinfunction "3_3") (pintype "passive"))
      (node (ref "BOOT_BUTTON") (pin "4") (pinfunction "4_4") (pintype "passive"))
      (node (ref "C6") (pin "1") (pinfunction "1_1") (pintype "passive"))
      (node (ref "R_BOOT") (pin "2") (pinfunction "2_2") (pintype "passive"))
      (node (ref "U2") (pin "15") (pinfunction "IO9_15") (pintype "bidirectional"))
    )
    (net (code "18") (name "IO{slash}CHANGE") (class "Default")
      (node (ref "C10") (pin "1") (pinfunction "1_1") (pintype "passive"))
      (node (ref "CHANGE_BUTTON") (pin "3") (pinfunction "3_3") (pintype "passive"))
      (node (ref "CHANGE_BUTTON") (pin "4") (pinfunction "4_4") (pintype "passive"))
      (node (ref "R_CHANGE") (pin "2") (pinfunction "2_2") (pintype "passive"))
      (node (ref "U2") (pin "23") (pinfunction "IO15_23") (pintype "bidirectional"))
    )
    (net (code "19") (name "MISO") (class "Default")
      (node (ref "D12") (pin "1") (pinfunction "1_1") (pintype "passive"))
      (node (ref "J4") (pin "P7") (pinfunction "DAT0_P7") (pintype "bidirectional"))
      (node (ref "MISO") (pin "TP") (pinfunction "TP_TP") (pintype "input"))
      (node (ref "R8") (pin "1") (pinfunction "1_1") (pintype "passive"))
      (node (ref "U1") (pin "2") (pinfunction "DO(IO1)_2") (pintype "bidirectional"))
      (node (ref "U2") (pin "27") (pinfunction "IO2_27") (pintype "bidirectional"))
    )
    (net (code "20") (name "MOSI") (class "Default")
      (node (ref "D11") (pin "1") (pinfunction "1_1") (pintype "passive"))
      (node (ref "J1") (pin "14") (pinfunction "14_14") (pintype "bidirectional"))
      (node (ref "J4") (pin "P3") (pinfunction "CMD_P3") (pintype "bidirectional"))
      (node (ref "MOSI") (pin "TP") (pinfunction "TP_TP") (pintype "input"))
      (node (ref "R7") (pin "1") (pinfunction "1_1") (pintype "passive"))
      (node (ref "U1") (pin "5") (pinfunction "DI(IO0)_5") (pintype "bidirectional"))
      (node (ref "U2") (pin "7") (pinfunction "IO7_7") (pintype "bidirectional"))
    )
    (net (code "21") (name "Net-(CHG_LED-PadC)") (class "Default")
      (node (ref "CHG_LED") (pin "C") (pinfunction "C_C") (pintype "passive"))
      (node (ref "R1_BAT") (pin "2") (pinfunction "2_2") (pintype "passive"))
    )
    (net (code "22") (name "Net-(D2-CATHODE)") (class "Default")
      (node (ref "C1_BAT1") (pin "1") (pinfunction "1_1") (pintype "passive"))
      (node (ref "D2") (pin "1") (pinfunction "CATHODE_1") (pintype "bidirectional"))
      (node (ref "IC4") (pin "1") (pinfunction "VIN_1") (pintype "bidirectional"))
      (node (ref "IC4") (pin "3") (pinfunction "CE_3") (pintype "bidirectional"))
      (node (ref "Q1") (pin "2") (pinfunction "S_2") (pintype "bidirectional"))
    )
    (net (code "23") (name "Net-(D3\\-A)") (class "Default")
      (node (ref "C4") (pin "1") (pinfunction "1_1") (pintype "passive"))
      (node (ref "D3\\") (pin "2") (pinfunction "A_2") (pintype "bidirectional"))
      (node (ref "D4") (pin "1") (pinfunction "K_1") (pintype "bidirectional"))
    )
    (net (code "24") (name "Net-(D7-CATHODE)") (class "Default")
      (node (ref "D7") (pin "1") (pinfunction "CATHODE_1") (pintype "bidirectional"))
      (node (ref "R_CAPACITOR") (pin "2") (pinfunction "2_2") (pintype "passive"))
    )
    (net (code "25") (name "Net-(EPD_C1-Pad1)") (class "Default")
      (node (ref "EPD_C1") (pin "1") (pinfunction "1_1") (pintype "passive"))
      (node (ref "J1") (pin "4") (pinfunction "4_4") (pintype "bidirectional"))
    )
    (net (code "26") (name "Net-(EPD_C2-Pad1)") (class "Default")
      (node (ref "EPD_C2") (pin "1") (pinfunction "1_1") (pintype "passive"))
      (node (ref "J1") (pin "5") (pinfunction "5_5") (pintype "bidirectional"))
    )
    (net (code "27") (name "Net-(EPD_C5-Pad1)") (class "Default")
      (node (ref "EPD_C5") (pin "1") (pinfunction "1_1") (pintype "passive"))
      (node (ref "J1") (pin "15") (pinfunction "15_15") (pintype "bidirectional"))
    )
    (net (code "28") (name "Net-(EPD_C6-Pad1)") (class "Default")
      (node (ref "EPD_C6") (pin "1") (pinfunction "1_1") (pintype "passive"))
      (node (ref "J1") (pin "18") (pinfunction "18_18") (pintype "bidirectional"))
    )
    (net (code "29") (name "Net-(EPD_C7-Pad1)") (class "Default")
      (node (ref "EPD_C7") (pin "1") (pinfunction "1_1") (pintype "passive"))
      (node (ref "J1") (pin "19") (pinfunction "19_19") (pintype "bidirectional"))
    )
    (net (code "30") (name "Net-(EPD_C8-Pad1)") (class "Default")
      (node (ref "EPD_C8") (pin "1") (pinfunction "1_1") (pintype "passive"))
      (node (ref "J1") (pin "20") (pinfunction "20_20") (pintype "bidirectional"))
    )
    (net (code "31") (name "Net-(EPD_C10-Pad1)") (class "Default")
      (node (ref "EPD_C10") (pin "1") (pinfunction "1_1") (pintype "passive"))
      (node (ref "J1") (pin "22") (pinfunction "22_22") (pintype "bidirectional"))
    )
    (net (code "32") (name "Net-(EPD_C12-Pad1)") (class "Default")
      (node (ref "EPD_C12") (pin "1") (pinfunction "1_1") (pintype "passive"))
      (node (ref "J1") (pin "24") (pinfunction "24_24") (pintype "bidirectional"))
    )
    (net (code "33") (name "Net-(IC1-CT)") (class "Default")
      (node (ref "C_DELAY") (pin "1") (pinfunction "1_1") (pintype "passive"))
      (node (ref "IC1") (pin "5") (pinfunction "CT_5") (pintype "bidirectional"))
    )
    (net (code "34") (name "Net-(J2-PadA5)") (class "Default")
      (node (ref "J2") (pin "A5") (pinfunction "A5_A5") (pintype "bidirectional"))
      (node (ref "R2-USB1") (pin "2") (pinfunction "2_2") (pintype "passive"))
    )
    (net (code "35") (name "Net-(J2-PadB5)") (class "Default")
      (node (ref "J2") (pin "B5") (pinfunction "B5_B5") (pintype "bidirectional"))
      (node (ref "R2-USB") (pin "1") (pinfunction "1_1") (pintype "passive"))
    )
    (net (code "36") (name "Net-(MCP73831-PROG)") (class "Default")
      (node (ref "MCP73831") (pin "5") (pinfunction "PROG_5") (pintype "input"))
      (node (ref "R2_BAT") (pin "2") (pinfunction "2_2") (pintype "passive"))
    )
    (net (code "37") (name "Net-(MCP73831-STAT)") (class "Default")
      (node (ref "MCP73831") (pin "1") (pinfunction "STAT_1") (pintype "output"))
      (node (ref "R1_BAT") (pin "1") (pinfunction "1_1") (pintype "passive"))
    )
    (net (code "38") (name "PREVGH") (class "Default")
      (node (ref "D5") (pin "1") (pinfunction "K_1") (pintype "bidirectional"))
      (node (ref "EPD_C9") (pin "1") (pinfunction "1_1") (pintype "passive"))
      (node (ref "J1") (pin "21") (pinfunction "21_21") (pintype "bidirectional"))
    )
    (net (code "39") (name "PREVGL") (class "Default")
      (node (ref "D4") (pin "2") (pinfunction "A_2") (pintype "bidirectional"))
      (node (ref "EPD_C11") (pin "1") (pinfunction "1_1") (pintype "passive"))
      (node (ref "J1") (pin "23") (pinfunction "23_23") (pintype "bidirectional"))
    )
    (net (code "40") (name "RESE") (class "Default")
      (node (ref "J1") (pin "3") (pinfunction "3_3") (pintype "bidirectional"))
      (node (ref "Q3") (pin "2") (pinfunction "S_2") (pintype "bidirectional"))
      (node (ref "R3") (pin "1") (pinfunction "1_1") (pintype "passive"))
    )
    (net (code "41") (name "RESE'") (class "Default")
      (node (ref "R2") (pin "2") (pinfunction "2_2") (pintype "passive"))
      (node (ref "R3") (pin "2") (pinfunction "2_2") (pintype "passive"))
      (node (ref "SJ1") (pin "2") (pinfunction "2_2") (pintype "passive"))
    )
    (net (code "42") (name "RESET") (class "Default")
      (node (ref "C5") (pin "1") (pinfunction "1_1") (pintype "passive"))
      (node (ref "IC1") (pin "1") (pinfunction "VOUT_1") (pintype "bidirectional"))
      (node (ref "RESET_BUTTON") (pin "3") (pinfunction "3_3") (pintype "passive"))
      (node (ref "RESET_BUTTON") (pin "4") (pinfunction "4_4") (pintype "passive"))
      (node (ref "R_RESET") (pin "2") (pinfunction "2_2") (pintype "passive"))
      (node (ref "U2") (pin "3") (pinfunction "EN_3") (pintype "input"))
    )
    (net (code "43") (name "RTC_RST") (class "Default")
      (node (ref "U2") (pin "16") (pinfunction "IO18_16") (pintype "bidirectional"))
      (node (ref "U3") (pin "4") (pinfunction "~{RST}_4") (pintype "input"))
    )
    (net (code "44") (name "RX") (class "Default")
      (node (ref "TP2") (pin "TP") (pinfunction "TP_TP") (pintype "input"))
      (node (ref "U2") (pin "24") (pinfunction "RXD0/GPIO17_24") (pintype "bidirectional"))
    )
    (net (code "45") (name "SCK") (class "Default")
      (node (ref "D10") (pin "1") (pinfunction "1_1") (pintype "passive"))
      (node (ref "J1") (pin "13") (pinfunction "13_13") (pintype "bidirectional"))
      (node (ref "J4") (pin "P5") (pinfunction "CLK_P5") (pintype "bidirectional"))
      (node (ref "R6") (pin "1") (pinfunction "1_1") (pintype "passive"))
      (node (ref "SCK") (pin "TP") (pinfunction "TP_TP") (pintype "input"))
      (node (ref "U1") (pin "6") (pinfunction "CLK_6") (pintype "input"))
      (node (ref "U2") (pin "6") (pinfunction "IO6_6") (pintype "bidirectional"))
    )
    (net (code "46") (name "SCL") (class "Default")
      (node (ref "J3") (pin "4") (pinfunction "4_4") (pintype "passive"))
      (node (ref "R2_PINH") (pin "1") (pinfunction "1_1") (pintype "passive"))
      (node (ref "SENSOR2") (pin "4") (pinfunction "SCK_4") (pintype "input"))
      (node (ref "U2") (pin "20") (pinfunction "IO22_20") (pintype "bidirectional"))
      (node (ref "U3") (pin "16") (pinfunction "SCL_16") (pintype "input"))
      (node (ref "U4") (pin "7") (pinfunction "SCL_7") (pintype "input"))
    )
    (net (code "47") (name "SDA") (class "Default")
      (node (ref "J3") (pin "3") (pinfunction "3_3") (pintype "passive"))
      (node (ref "R1_PINH") (pin "1") (pinfunction "1_1") (pintype "passive"))
      (node (ref "SENSOR2") (pin "3") (pinfunction "SDI_3") (pintype "bidirectional"))
      (node (ref "U2") (pin "19") (pinfunction "IO21_19") (pintype "bidirectional"))
      (node (ref "U3") (pin "15") (pinfunction "SDA_15") (pintype "bidirectional"))
      (node (ref "U4") (pin "8") (pinfunction "SDA_8") (pintype "bidirectional"))
    )
    (net (code "48") (name "SRC") (class "Default")
      (node (ref "C4") (pin "2") (pinfunction "2_2") (pintype "passive"))
      (node (ref "D5") (pin "2") (pinfunction "A_2") (pintype "bidirectional"))
      (node (ref "L1") (pin "1") (pinfunction "1_1") (pintype "passive"))
      (node (ref "Q3") (pin "3") (pinfunction "D_3") (pintype "bidirectional"))
    )
    (net (code "49") (name "SS_SD") (class "Default")
      (node (ref "D8") (pin "1") (pinfunction "1_1") (pintype "passive"))
      (node (ref "J4") (pin "P2") (pinfunction "CD/DAT3_P2") (pintype "bidirectional"))
      (node (ref "R10") (pin "1") (pinfunction "1_1") (pintype "passive"))
      (node (ref "U2") (pin "4") (pinfunction "IO4_4") (pintype "bidirectional"))
    )
    (net (code "50") (name "TX") (class "Default")
      (node (ref "TP1") (pin "TP") (pinfunction "TP_TP") (pintype "input"))
      (node (ref "U2") (pin "25") (pinfunction "TXD0/GPIO16_25") (pintype "bidirectional"))
    )
    (net (code "51") (name "USB_D+") (class "Default")
      (node (ref "D1") (pin "1") (pinfunction "I/O1_1_1") (pintype "bidirectional"))
      (node (ref "U2") (pin "14") (pinfunction "IO13_14") (pintype "bidirectional"))
    )
    (net (code "52") (name "USB_D-") (class "Default")
      (node (ref "D1") (pin "3") (pinfunction "I/O2_1_3") (pintype "bidirectional"))
      (node (ref "U2") (pin "13") (pinfunction "IO12_13") (pintype "bidirectional"))
    )
    (net (code "53") (name "VBAT") (class "Default")
      (node (ref "C2_BAT") (pin "1") (pinfunction "1_1") (pintype "passive"))
      (node (ref "MCP73831") (pin "3") (pinfunction "VBAT_3") (pintype "power_in"))
      (node (ref "Q1") (pin "3") (pinfunction "D_3") (pintype "bidirectional"))
      (node (ref "TP3") (pin "TP") (pinfunction "TP_TP") (pintype "input"))
      (node (ref "U4") (pin "2") (pinfunction "CELL_2") (pintype "power_in"))
      (node (ref "U4") (pin "3") (pinfunction "VDD_3") (pintype "power_in"))
    )
    (net (code "54") (name "VBUS") (class "Default")
      (node (ref "C1_BAT") (pin "1") (pinfunction "1_1") (pintype "passive"))
      (node (ref "C4_USB") (pin "1") (pinfunction "1_1") (pintype "passive"))
      (node (ref "C5_USB") (pin "1") (pinfunction "1_1") (pintype "passive"))
      (node (ref "CHG_LED") (pin "A") (pinfunction "A_A") (pintype "passive"))
      (node (ref "D1") (pin "5") (pinfunction "VBUS_5") (pintype "bidirectional"))
      (node (ref "D2") (pin "2") (pinfunction "ANODE_2") (pintype "bidirectional"))
      (node (ref "MCP73831") (pin "4") (pinfunction "VIN_4") (pintype "power_in"))
      (node (ref "PFMF.050.1") (pin "2") (pinfunction "2_2") (pintype "passive"))
      (node (ref "Q1") (pin "1") (pinfunction "G_1") (pintype "bidirectional"))
      (node (ref "R1_PWRUSB") (pin "2") (pinfunction "2_2") (pintype "passive"))
      (node (ref "VBUS") (pin "TP") (pinfunction "TP_TP") (pintype "input"))
    )
    (net (code "55") (name "VRTC") (class "Default")
      (node (ref "C10_SUPERCAP") (pin "2") (pinfunction "2_2") (pintype "passive"))
      (node (ref "C8") (pin "1") (pinfunction "1_1") (pintype "passive"))
      (node (ref "R_CAPACITOR") (pin "1") (pinfunction "1_1") (pintype "passive"))
      (node (ref "U3") (pin "14") (pinfunction "VBAT_14") (pintype "power_in"))
    )
    (net (code "56") (name "VUSB") (class "Default")
      (node (ref "J2") (pin "A4") (pinfunction "A4_A4") (pintype "bidirectional"))
      (node (ref "J2") (pin "A9") (pinfunction "A9_A9") (pintype "bidirectional"))
      (node (ref "J2") (pin "B4") (pinfunction "B4_B4") (pintype "bidirectional"))
      (node (ref "J2") (pin "B9") (pinfunction "B9_B9") (pintype "bidirectional"))
      (node (ref "PFMF.050.1") (pin "1") (pinfunction "1_1") (pintype "passive"))
    )
    (net (code "57") (name "unconnected-(IC1-NC-Pad4)") (class "Default")
      (node (ref "IC1") (pin "4") (pinfunction "NC_4") (pintype "no_connect"))
    )
    (net (code "58") (name "unconnected-(IC4-NC-Pad4)") (class "Default")
      (node (ref "IC4") (pin "4") (pinfunction "NC_4") (pintype "no_connect"))
    )
    (net (code "59") (name "unconnected-(J1-Pad1)") (class "Default")
      (node (ref "J1") (pin "1") (pinfunction "1_1") (pintype "bidirectional"))
    )
    (net (code "60") (name "unconnected-(J1-Pad6)") (class "Default")
      (node (ref "J1") (pin "6") (pinfunction "6_6") (pintype "bidirectional"))
    )
    (net (code "61") (name "unconnected-(J1-Pad7)") (class "Default")
      (node (ref "J1") (pin "7") (pinfunction "7_7") (pintype "bidirectional"))
    )
    (net (code "62") (name "unconnected-(J2-PadA8)") (class "Default")
      (node (ref "J2") (pin "A8") (pinfunction "A8_A8") (pintype "bidirectional"))
    )
    (net (code "63") (name "unconnected-(J2-PadB8)") (class "Default")
      (node (ref "J2") (pin "B8") (pinfunction "B8_B8") (pintype "bidirectional"))
    )
    (net (code "64") (name "unconnected-(J4-DAT1-PadP8)") (class "Default")
      (node (ref "J4") (pin "P8") (pinfunction "DAT1_P8") (pintype "bidirectional"))
    )
    (net (code "65") (name "unconnected-(J4-DAT2-PadP1)") (class "Default")
      (node (ref "J4") (pin "P1") (pinfunction "DAT2_P1") (pintype "bidirectional"))
    )
    (net (code "66") (name "unconnected-(J4-DETECTION_1-PadS1)") (class "Default")
      (node (ref "J4") (pin "S1") (pinfunction "DETECTION_1_S1") (pintype "bidirectional"))
    )
    (net (code "67") (name "unconnected-(J4-DETECTION_2-PadS2)") (class "Default")
      (node (ref "J4") (pin "S2") (pinfunction "DETECTION_2_S2") (pintype "bidirectional"))
    )
    (net (code "68") (name "unconnected-(U2-NC-Pad22)") (class "Default")
      (node (ref "U2") (pin "22") (pinfunction "NC_22") (pintype "no_connect"))
    )
    (net (code "69") (name "unconnected-(U4-~{ALERT}-Pad5)") (class "Default")
      (node (ref "U4") (pin "5") (pinfunction "~{ALERT}_5") (pintype "output"))
    )
  )
)
